# schematic.net
KiCad netlist of a schematic drawn in Altium Designer
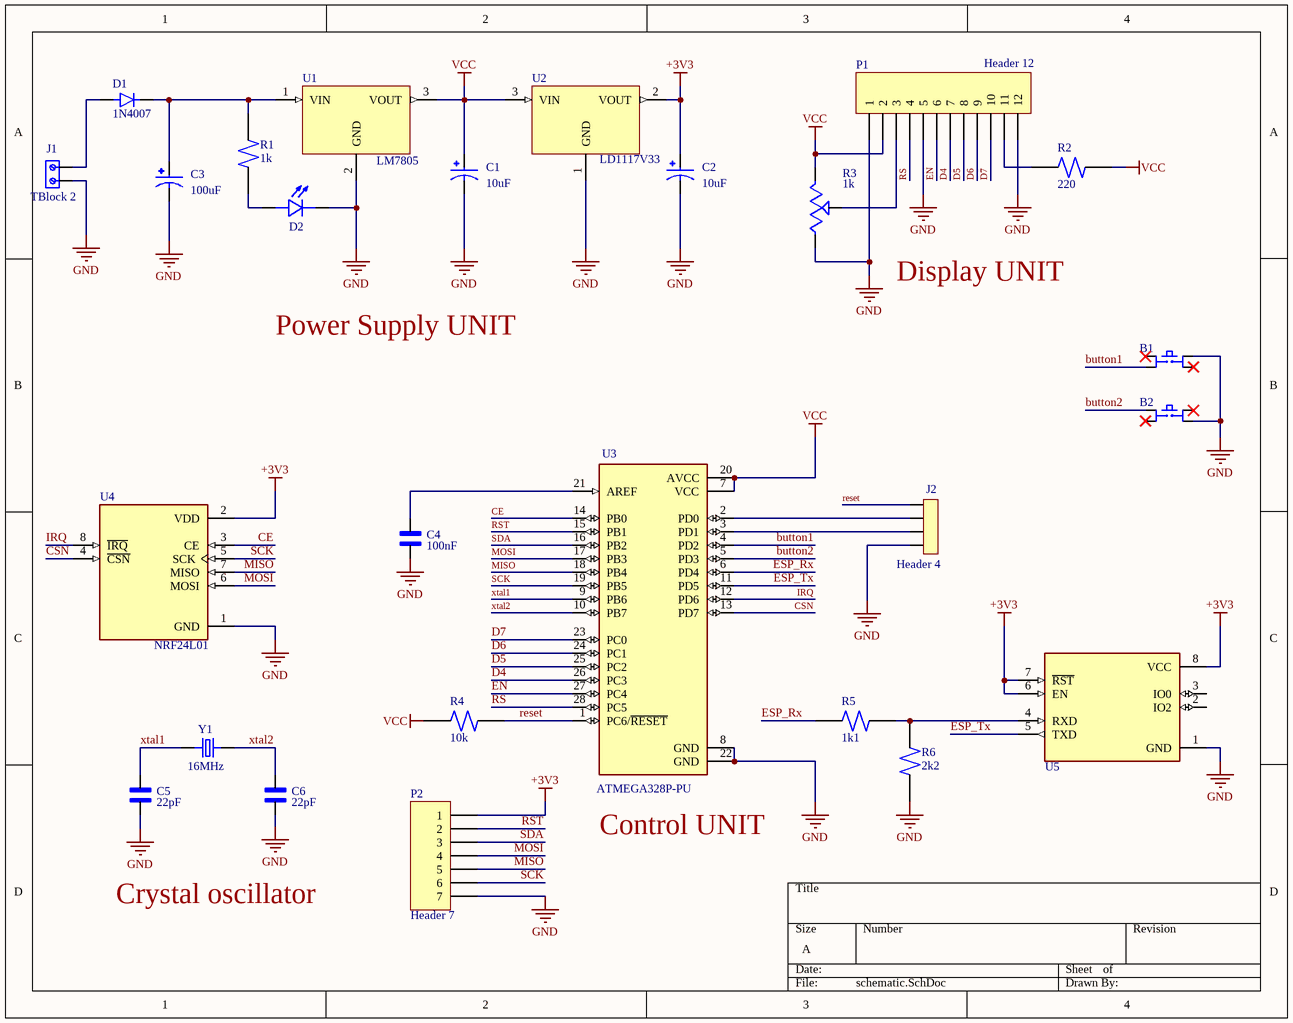
[diagram p0: schematic.SchDoc]

(export (version "E")
  (design (tool "Eeschema 10.0.6"))
  (components
    (comp (ref "B1")
      (value "Push button")
      (footprint "SW_TS02-66-95-BK-260-LCR-D")
      (libsource (lib "Installed library") (part "Push button"))
    )
    (comp (ref "B2")
      (value "Push button")
      (footprint "SW_TS02-66-95-BK-260-LCR-D")
      (libsource (lib "Installed library") (part "Push button"))
    )
    (comp (ref "C1")
      (value "10uF")
      (footprint "CAPPRD500W50D500H1100")
      (description "FS-A")
      (fields (field (name "MF") "{'manufacturer': u'Panasonic'}") (field (name "MP") "EEUFS0J221B"))
      (libsource (lib "Installed library") (part "Electrolytic capacitor"))
    )
    (comp (ref "C2")
      (value "10uF")
      (footprint "CAPPRD500W50D500H1100")
      (description "FS-A")
      (fields (field (name "MF") "{'manufacturer': u'Panasonic'}") (field (name "MP") "EEUFS0J221B"))
      (libsource (lib "Installed library") (part "Electrolytic capacitor"))
    )
    (comp (ref "C3")
      (value "100uF")
      (footprint "CAPPRD500W50D500H1100")
      (description "FS-A")
      (fields (field (name "MF") "{'manufacturer': u'Panasonic'}") (field (name "MP") "EEUFS0J221B"))
      (libsource (lib "") (part "Electrolytic capacitor_1"))
    )
    (comp (ref "C4")
      (value "100nF")
      (footprint "CAPRB500W50L450T300H550")
      (description "2200 pF Â±10% 250V Ceramic Capacitor X7R Radial")
      (fields (field (name "DIGI-KEY_PART_NUMBER") "445-173386-1-ND") (field (name "MF") "TDK"))
      (libsource (lib "Installed library") (part "Ceramic capacitor"))
    )
    (comp (ref "C5")
      (value "22pF")
      (footprint "CAPRB500W50L450T300H550")
      (description "2200 pF Â±10% 250V Ceramic Capacitor X7R Radial")
      (fields (field (name "DIGI-KEY_PART_NUMBER") "445-173386-1-ND") (field (name "MF") "TDK"))
      (libsource (lib "Installed library") (part "Ceramic capacitor"))
    )
    (comp (ref "C6")
      (value "22pF")
      (footprint "CAPRB500W50L450T300H550")
      (description "2200 pF Â±10% 250V Ceramic Capacitor X7R Radial")
      (fields (field (name "DIGI-KEY_PART_NUMBER") "445-173386-1-ND") (field (name "MF") "TDK"))
      (libsource (lib "Installed library") (part "Ceramic capacitor"))
    )
    (comp (ref "D1")
      (value "1N4007")
      (footprint "DIOAD1060W80L520D270")
      (description "Diode Switching 1KV 1A 2-Pin DO-41")
      (libsource (lib "Components") (part "1N4007"))
    )
    (comp (ref "D2")
      (value "L08R5000Q1")
      (footprint "LEDRD254W57D500H1070")
      (description "LED, Orange, Through Hole, T-1 3/4 (5mm), 30 mA, 2.1 V, 635 nm")
      (fields (field (name "MF") "{'manufacturer': u'LED Technology'}"))
      (libsource (lib "Installed library") (part "LED"))
    )
    (comp (ref "J1")
      (value "TBlock 2")
      (footprint "691111710002")
      (description "2 Position Wire to Board Terminal Block Horizontal with Board 0.197 _5.00mm_ Through Hole")
      (fields (field (name "MP") "691111710002") (field (name "MF") "Wurth Electronics"))
      (libsource (lib "Installed library") (part "Terminal Block - 2Pins"))
    )
    (comp (ref "J2")
      (value "Header 4")
      (footprint "SULLINS_PPTC041LFBN-RC")
      (description "4 Position Header Connector Through Hole")
      (fields (field (name "MP") "PPTC041LFBN-RC") (field (name "MF") "Sullins Connector"))
      (libsource (lib "Installed library") (part "Female header - 4Pins"))
    )
    (comp (ref "P1")
      (value "Header 12")
      (footprint "HDR1X12")
      (description "Header, 12-Pin")
      (fields (field (name "PUBLISHER") "Altium Limited"))
      (libsource (lib "Miscellaneous Connectors") (part "Header 12"))
    )
    (comp (ref "P2")
      (value "Header 7")
      (footprint "HDR1X7")
      (description "Header, 7-Pin")
      (fields (field (name "PUBLISHER") "Altium Limited"))
      (libsource (lib "Miscellaneous Connectors") (part "Header 7"))
    )
    (comp (ref "R1")
      (value "1k")
      (footprint "RESAD1100W55L680D260")
      (description "(MFR-25FBF52-10K) 10,2 kOhm bei 1% 0,25W, 1/4W Durchbohrlochwiderstand Axial Metal Film")
      (fields (field (name "DIGI-KEY_PART_NUMBER") "10.2KXBK-ND") (field (name "MF") "Yageo"))
      (libsource (lib "Installed library") (part "Resistor (0.25W)"))
    )
    (comp (ref "R2")
      (value "220")
      (footprint "RESAD1100W55L680D260")
      (description "(MFR-25FBF52-10K) 10,2 kOhm bei 1% 0,25W, 1/4W Durchbohrlochwiderstand Axial Metal Film")
      (fields (field (name "DIGI-KEY_PART_NUMBER") "10.2KXBK-ND") (field (name "MF") "Yageo"))
      (libsource (lib "Installed library") (part "Resistor (0.25W)"))
    )
    (comp (ref "R3")
      (value "1k")
      (footprint "TRIM_3306F-1-105")
      (fields (field (name "MF") "Bourns") (field (name "MP") "3306F-1-105"))
      (libsource (lib "Installed library") (part "Potentiometer1"))
    )
    (comp (ref "R4")
      (value "10k")
      (footprint "RESAD1100W55L680D260")
      (description "(MFR-25FBF52-10K) 10,2 kOhm bei 1% 0,25W, 1/4W Durchbohrlochwiderstand Axial Metal Film")
      (fields (field (name "DIGI-KEY_PART_NUMBER") "10.2KXBK-ND") (field (name "MF") "Yageo"))
      (libsource (lib "Installed library") (part "Resistor (0.25W)"))
    )
    (comp (ref "R5")
      (value "1k1")
      (footprint "RESAD1100W55L680D260")
      (description "(MFR-25FBF52-10K) 10,2 kOhm bei 1% 0,25W, 1/4W Durchbohrlochwiderstand Axial Metal Film")
      (fields (field (name "DIGI-KEY_PART_NUMBER") "10.2KXBK-ND") (field (name "MF") "Yageo"))
      (libsource (lib "Installed library") (part "Resistor (0.25W)"))
    )
    (comp (ref "R6")
      (value "2k2")
      (footprint "RESAD1100W55L680D260")
      (description "(MFR-25FBF52-10K) 10,2 kOhm bei 1% 0,25W, 1/4W Durchbohrlochwiderstand Axial Metal Film")
      (fields (field (name "DIGI-KEY_PART_NUMBER") "10.2KXBK-ND") (field (name "MF") "Yageo"))
      (libsource (lib "Installed library") (part "Resistor (0.25W)"))
    )
    (comp (ref "U1")
      (value "LM7805")
      (footprint "TO255P1020X450X1968-3")
      (fields (field (name "MP") "LM7805CT/NOPB"))
      (libsource (lib "Voltage regulator") (part "LM78__"))
    )
    (comp (ref "U2")
      (value "LD1117V33")
      (footprint "TO255P1020X450X1968-3")
      (libsource (lib "Voltage regulator") (part "LD1117V33"))
    )
    (comp (ref "U3")
      (value "ATMEGA328P-PU")
      (footprint "DIP794W46P254L2967H457Q28B")
      (description "ATmega Series 20 MHz 32 KB Flash 2 KB SRAM 8-Bit Microcontroller - DIP-28")
      (libsource (lib "Installed library") (part "ATMEGA328P-PU"))
    )
    (comp (ref "U4")
      (value "NRF24L01")
      (footprint "XCVR_NRF24L01P-MODULE-PCB")
      (description "- Transceiver For Use With nRF24L01+")
      (fields (field (name "MP") "NRF24L01P-MODULE-PCB") (field (name "MF") "Nordic Semiconductor"))
      (libsource (lib "Modules") (part "NRF24L01P-MODULE-PCB"))
    )
    (comp (ref "U5")
      (value "ESP8266-01/ESP-01")
      (footprint "XCVR_ESP8266-01/ESP-01")
      (libsource (lib "Installed library") (part "ESP8266-01 Module"))
    )
    (comp (ref "Y1")
      (value "16MHz")
      (footprint "XTAL_ECS-160-20-4X")
      (description "CRYSTAL T/H")
      (fields (field (name "MF") "{'manufacturer': u'ECS Inc.'}") (field (name "MP") "ECS-160-S-4"))
      (libsource (lib "Installed library") (part "Crystal oscilator"))
    )
  )
  (nets
    (net (code "1") (name "+3V3") (class "Default")
      (node (ref "C2") (pin "P") (pinfunction "P_P") (pintype "passive"))
      (node (ref "P2") (pin "1") (pinfunction "1_1") (pintype "passive"))
      (node (ref "U2") (pin "2") (pinfunction "VOUT_2") (pintype "output"))
      (node (ref "U4") (pin "2") (pinfunction "VDD_2") (pintype "power_in"))
      (node (ref "U5") (pin "6") (pinfunction "EN_6") (pintype "input"))
      (node (ref "U5") (pin "7") (pinfunction "~{RST}_7") (pintype "input"))
      (node (ref "U5") (pin "8") (pinfunction "VCC_8") (pintype "power_in"))
    )
    (net (code "2") (name "/CE") (class "Default")
      (node (ref "U3") (pin "14") (pinfunction "PB0_14") (pintype "bidirectional"))
      (node (ref "U4") (pin "3") (pinfunction "CE_3") (pintype "input"))
    )
    (net (code "3") (name "/CSN") (class "Default")
      (node (ref "U3") (pin "13") (pinfunction "PD7_13") (pintype "bidirectional"))
      (node (ref "U4") (pin "4") (pinfunction "~{CSN}_4") (pintype "input"))
    )
    (net (code "4") (name "/D4") (class "Default")
      (node (ref "P1") (pin "7") (pinfunction "7_7") (pintype "passive"))
      (node (ref "U3") (pin "26") (pinfunction "PC3_26") (pintype "bidirectional"))
    )
    (net (code "5") (name "/D5") (class "Default")
      (node (ref "P1") (pin "8") (pinfunction "8_8") (pintype "passive"))
      (node (ref "U3") (pin "25") (pinfunction "PC2_25") (pintype "bidirectional"))
    )
    (net (code "6") (name "/D6") (class "Default")
      (node (ref "P1") (pin "9") (pinfunction "9_9") (pintype "passive"))
      (node (ref "U3") (pin "24") (pinfunction "PC1_24") (pintype "bidirectional"))
    )
    (net (code "7") (name "/D7") (class "Default")
      (node (ref "P1") (pin "10") (pinfunction "10_10") (pintype "passive"))
      (node (ref "U3") (pin "23") (pinfunction "PC0_23") (pintype "bidirectional"))
    )
    (net (code "8") (name "/EN") (class "Default")
      (node (ref "P1") (pin "6") (pinfunction "6_6") (pintype "passive"))
      (node (ref "U3") (pin "27") (pinfunction "PC4_27") (pintype "bidirectional"))
    )
    (net (code "9") (name "/ESP_Rx") (class "Default")
      (node (ref "R5") (pin "2") (pinfunction "2_2") (pintype "passive"))
      (node (ref "U3") (pin "6") (pinfunction "PD4_6") (pintype "bidirectional"))
    )
    (net (code "10") (name "/ESP_Tx") (class "Default")
      (node (ref "U3") (pin "11") (pinfunction "PD5_11") (pintype "bidirectional"))
      (node (ref "U5") (pin "5") (pinfunction "TXD_5") (pintype "output"))
    )
    (net (code "11") (name "/IRQ") (class "Default")
      (node (ref "U3") (pin "12") (pinfunction "PD6_12") (pintype "bidirectional"))
      (node (ref "U4") (pin "8") (pinfunction "~{IRQ}_8") (pintype "input"))
    )
    (net (code "12") (name "/MISO") (class "Default")
      (node (ref "P2") (pin "5") (pinfunction "5_5") (pintype "passive"))
      (node (ref "U3") (pin "18") (pinfunction "PB4_18") (pintype "bidirectional"))
      (node (ref "U4") (pin "7") (pinfunction "MISO_7") (pintype "input"))
    )
    (net (code "13") (name "/MOSI") (class "Default")
      (node (ref "P2") (pin "4") (pinfunction "4_4") (pintype "passive"))
      (node (ref "U3") (pin "17") (pinfunction "PB3_17") (pintype "bidirectional"))
      (node (ref "U4") (pin "6") (pinfunction "MOSI_6") (pintype "input"))
    )
    (net (code "14") (name "/RS") (class "Default")
      (node (ref "P1") (pin "4") (pinfunction "4_4") (pintype "passive"))
      (node (ref "U3") (pin "28") (pinfunction "PC5_28") (pintype "bidirectional"))
    )
    (net (code "15") (name "/RST") (class "Default")
      (node (ref "P2") (pin "2") (pinfunction "2_2") (pintype "passive"))
      (node (ref "U3") (pin "15") (pinfunction "PB1_15") (pintype "bidirectional"))
    )
    (net (code "16") (name "/SCK") (class "Default")
      (node (ref "P2") (pin "6") (pinfunction "6_6") (pintype "passive"))
      (node (ref "U3") (pin "19") (pinfunction "PB5_19") (pintype "bidirectional"))
      (node (ref "U4") (pin "5") (pinfunction "SCK_5") (pintype "input"))
    )
    (net (code "17") (name "/SDA") (class "Default")
      (node (ref "P2") (pin "3") (pinfunction "3_3") (pintype "passive"))
      (node (ref "U3") (pin "16") (pinfunction "PB2_16") (pintype "bidirectional"))
    )
    (net (code "18") (name "/button1") (class "Default")
      (node (ref "B1") (pin "2") (pinfunction "2_2") (pintype "passive"))
      (node (ref "U3") (pin "4") (pinfunction "PD2_4") (pintype "bidirectional"))
    )
    (net (code "19") (name "/button2") (class "Default")
      (node (ref "B2") (pin "1") (pinfunction "1_1") (pintype "passive"))
      (node (ref "U3") (pin "5") (pinfunction "PD3_5") (pintype "bidirectional"))
    )
    (net (code "20") (name "/reset") (class "Default")
      (node (ref "J2") (pin "4") (pinfunction "4_4") (pintype "passive"))
      (node (ref "R4") (pin "1") (pinfunction "1_1") (pintype "passive"))
      (node (ref "U3") (pin "1") (pinfunction "PC6/~{RESET}_1") (pintype "bidirectional"))
    )
    (net (code "21") (name "/xtal1") (class "Default")
      (node (ref "C5") (pin "1") (pinfunction "1_1") (pintype "passive"))
      (node (ref "U3") (pin "9") (pinfunction "PB6_9") (pintype "bidirectional"))
      (node (ref "Y1") (pin "1") (pinfunction "1_1") (pintype "passive"))
    )
    (net (code "22") (name "/xtal2") (class "Default")
      (node (ref "C6") (pin "1") (pinfunction "1_1") (pintype "passive"))
      (node (ref "U3") (pin "10") (pinfunction "PB7_10") (pintype "bidirectional"))
      (node (ref "Y1") (pin "2") (pinfunction "2_2") (pintype "passive"))
    )
    (net (code "23") (name "GND") (class "Default")
      (node (ref "B1") (pin "3") (pinfunction "3_3") (pintype "passive"))
      (node (ref "B2") (pin "4") (pinfunction "4_4") (pintype "passive"))
      (node (ref "C1") (pin "N") (pinfunction "N_N") (pintype "passive"))
      (node (ref "C2") (pin "N") (pinfunction "N_N") (pintype "passive"))
      (node (ref "C3") (pin "N") (pinfunction "N_N") (pintype "passive"))
      (node (ref "C4") (pin "2") (pinfunction "2_2") (pintype "passive"))
      (node (ref "C5") (pin "2") (pinfunction "2_2") (pintype "passive"))
      (node (ref "C6") (pin "2") (pinfunction "2_2") (pintype "passive"))
      (node (ref "D2") (pin "C") (pinfunction "C_C") (pintype "passive"))
      (node (ref "J1") (pin "1") (pinfunction "1_1") (pintype "passive"))
      (node (ref "J2") (pin "1") (pinfunction "1_1") (pintype "passive"))
      (node (ref "P1") (pin "1") (pinfunction "1_1") (pintype "passive"))
      (node (ref "P1") (pin "12") (pinfunction "12_12") (pintype "passive"))
      (node (ref "P1") (pin "5") (pinfunction "5_5") (pintype "passive"))
      (node (ref "P2") (pin "7") (pinfunction "7_7") (pintype "passive"))
      (node (ref "R3") (pin "1") (pinfunction "CCW_1") (pintype "passive"))
      (node (ref "R6") (pin "1") (pinfunction "1_1") (pintype "passive"))
      (node (ref "U1") (pin "2") (pinfunction "GND_2") (pintype "passive"))
      (node (ref "U2") (pin "1") (pinfunction "GND_1") (pintype "passive"))
      (node (ref "U3") (pin "22") (pinfunction "GND_22") (pintype "power_in"))
      (node (ref "U3") (pin "8") (pinfunction "GND_8") (pintype "power_in"))
      (node (ref "U4") (pin "1") (pinfunction "GND_1") (pintype "power_in"))
      (node (ref "U5") (pin "1") (pinfunction "GND_1") (pintype "power_in"))
    )
    (net (code "24") (name "Net-(D1-PadA)") (class "Default")
      (node (ref "D1") (pin "A") (pinfunction "A_A") (pintype "passive"))
      (node (ref "J1") (pin "2") (pinfunction "2_2") (pintype "passive"))
    )
    (net (code "25") (name "Net-(D2-PadA)") (class "Default")
      (node (ref "D2") (pin "A") (pinfunction "A_A") (pintype "passive"))
      (node (ref "R1") (pin "1") (pinfunction "1_1") (pintype "passive"))
    )
    (net (code "26") (name "Net-(P1-Pad11)") (class "Default")
      (node (ref "P1") (pin "11") (pinfunction "11_11") (pintype "passive"))
      (node (ref "R2") (pin "2") (pinfunction "2_2") (pintype "passive"))
    )
    (net (code "27") (name "Net-(R3-WIPER)") (class "Default")
      (node (ref "P1") (pin "3") (pinfunction "3_3") (pintype "passive"))
      (node (ref "R3") (pin "2") (pinfunction "WIPER_2") (pintype "passive"))
    )
    (net (code "28") (name "Net-(U1-VIN)") (class "Default")
      (node (ref "C3") (pin "P") (pinfunction "P_P") (pintype "passive"))
      (node (ref "D1") (pin "C") (pinfunction "C_C") (pintype "passive"))
      (node (ref "R1") (pin "2") (pinfunction "2_2") (pintype "passive"))
      (node (ref "U1") (pin "1") (pinfunction "VIN_1") (pintype "input"))
    )
    (net (code "29") (name "Net-(U3-AREF)") (class "Default")
      (node (ref "C4") (pin "1") (pinfunction "1_1") (pintype "passive"))
      (node (ref "U3") (pin "21") (pinfunction "AREF_21") (pintype "input"))
    )
    (net (code "30") (name "Net-(U3-PD0)") (class "Default")
      (node (ref "J2") (pin "3") (pinfunction "3_3") (pintype "passive"))
      (node (ref "U3") (pin "2") (pinfunction "PD0_2") (pintype "bidirectional"))
    )
    (net (code "31") (name "Net-(U3-PD1)") (class "Default")
      (node (ref "J2") (pin "2") (pinfunction "2_2") (pintype "passive"))
      (node (ref "U3") (pin "3") (pinfunction "PD1_3") (pintype "bidirectional"))
    )
    (net (code "32") (name "Net-(U5-RXD)") (class "Default")
      (node (ref "R5") (pin "1") (pinfunction "1_1") (pintype "passive"))
      (node (ref "R6") (pin "2") (pinfunction "2_2") (pintype "passive"))
      (node (ref "U5") (pin "4") (pinfunction "RXD_4") (pintype "input"))
    )
    (net (code "33") (name "VCC") (class "Default")
      (node (ref "C1") (pin "P") (pinfunction "P_P") (pintype "passive"))
      (node (ref "P1") (pin "2") (pinfunction "2_2") (pintype "passive"))
      (node (ref "R2") (pin "1") (pinfunction "1_1") (pintype "passive"))
      (node (ref "R3") (pin "3") (pinfunction "CW_3") (pintype "passive"))
      (node (ref "R4") (pin "2") (pinfunction "2_2") (pintype "passive"))
      (node (ref "U1") (pin "3") (pinfunction "VOUT_3") (pintype "output"))
      (node (ref "U2") (pin "3") (pinfunction "VIN_3") (pintype "input"))
      (node (ref "U3") (pin "20") (pinfunction "AVCC_20") (pintype "power_in"))
      (node (ref "U3") (pin "7") (pinfunction "VCC_7") (pintype "power_in"))
    )
    (net (code "34") (name "unconnected-(B1-Pad1)") (class "Default")
      (node (ref "B1") (pin "1") (pinfunction "1_1") (pintype "passive+no_connect"))
    )
    (net (code "35") (name "unconnected-(B1-Pad4)") (class "Default")
      (node (ref "B1") (pin "4") (pinfunction "4_4") (pintype "passive+no_connect"))
    )
    (net (code "36") (name "unconnected-(B2-Pad2)") (class "Default")
      (node (ref "B2") (pin "2") (pinfunction "2_2") (pintype "passive+no_connect"))
    )
    (net (code "37") (name "unconnected-(B2-Pad3)") (class "Default")
      (node (ref "B2") (pin "3") (pinfunction "3_3") (pintype "passive+no_connect"))
    )
    (net (code "38") (name "unconnected-(U5-IO0-Pad3)") (class "Default")
      (node (ref "U5") (pin "3") (pinfunction "IO0_3") (pintype "bidirectional"))
    )
    (net (code "39") (name "unconnected-(U5-IO2-Pad2)") (class "Default")
      (node (ref "U5") (pin "2") (pinfunction "IO2_2") (pintype "bidirectional"))
    )
  )
)
